# FeedbackLoop.net
KiCad netlist of a schematic drawn in Altium Designer
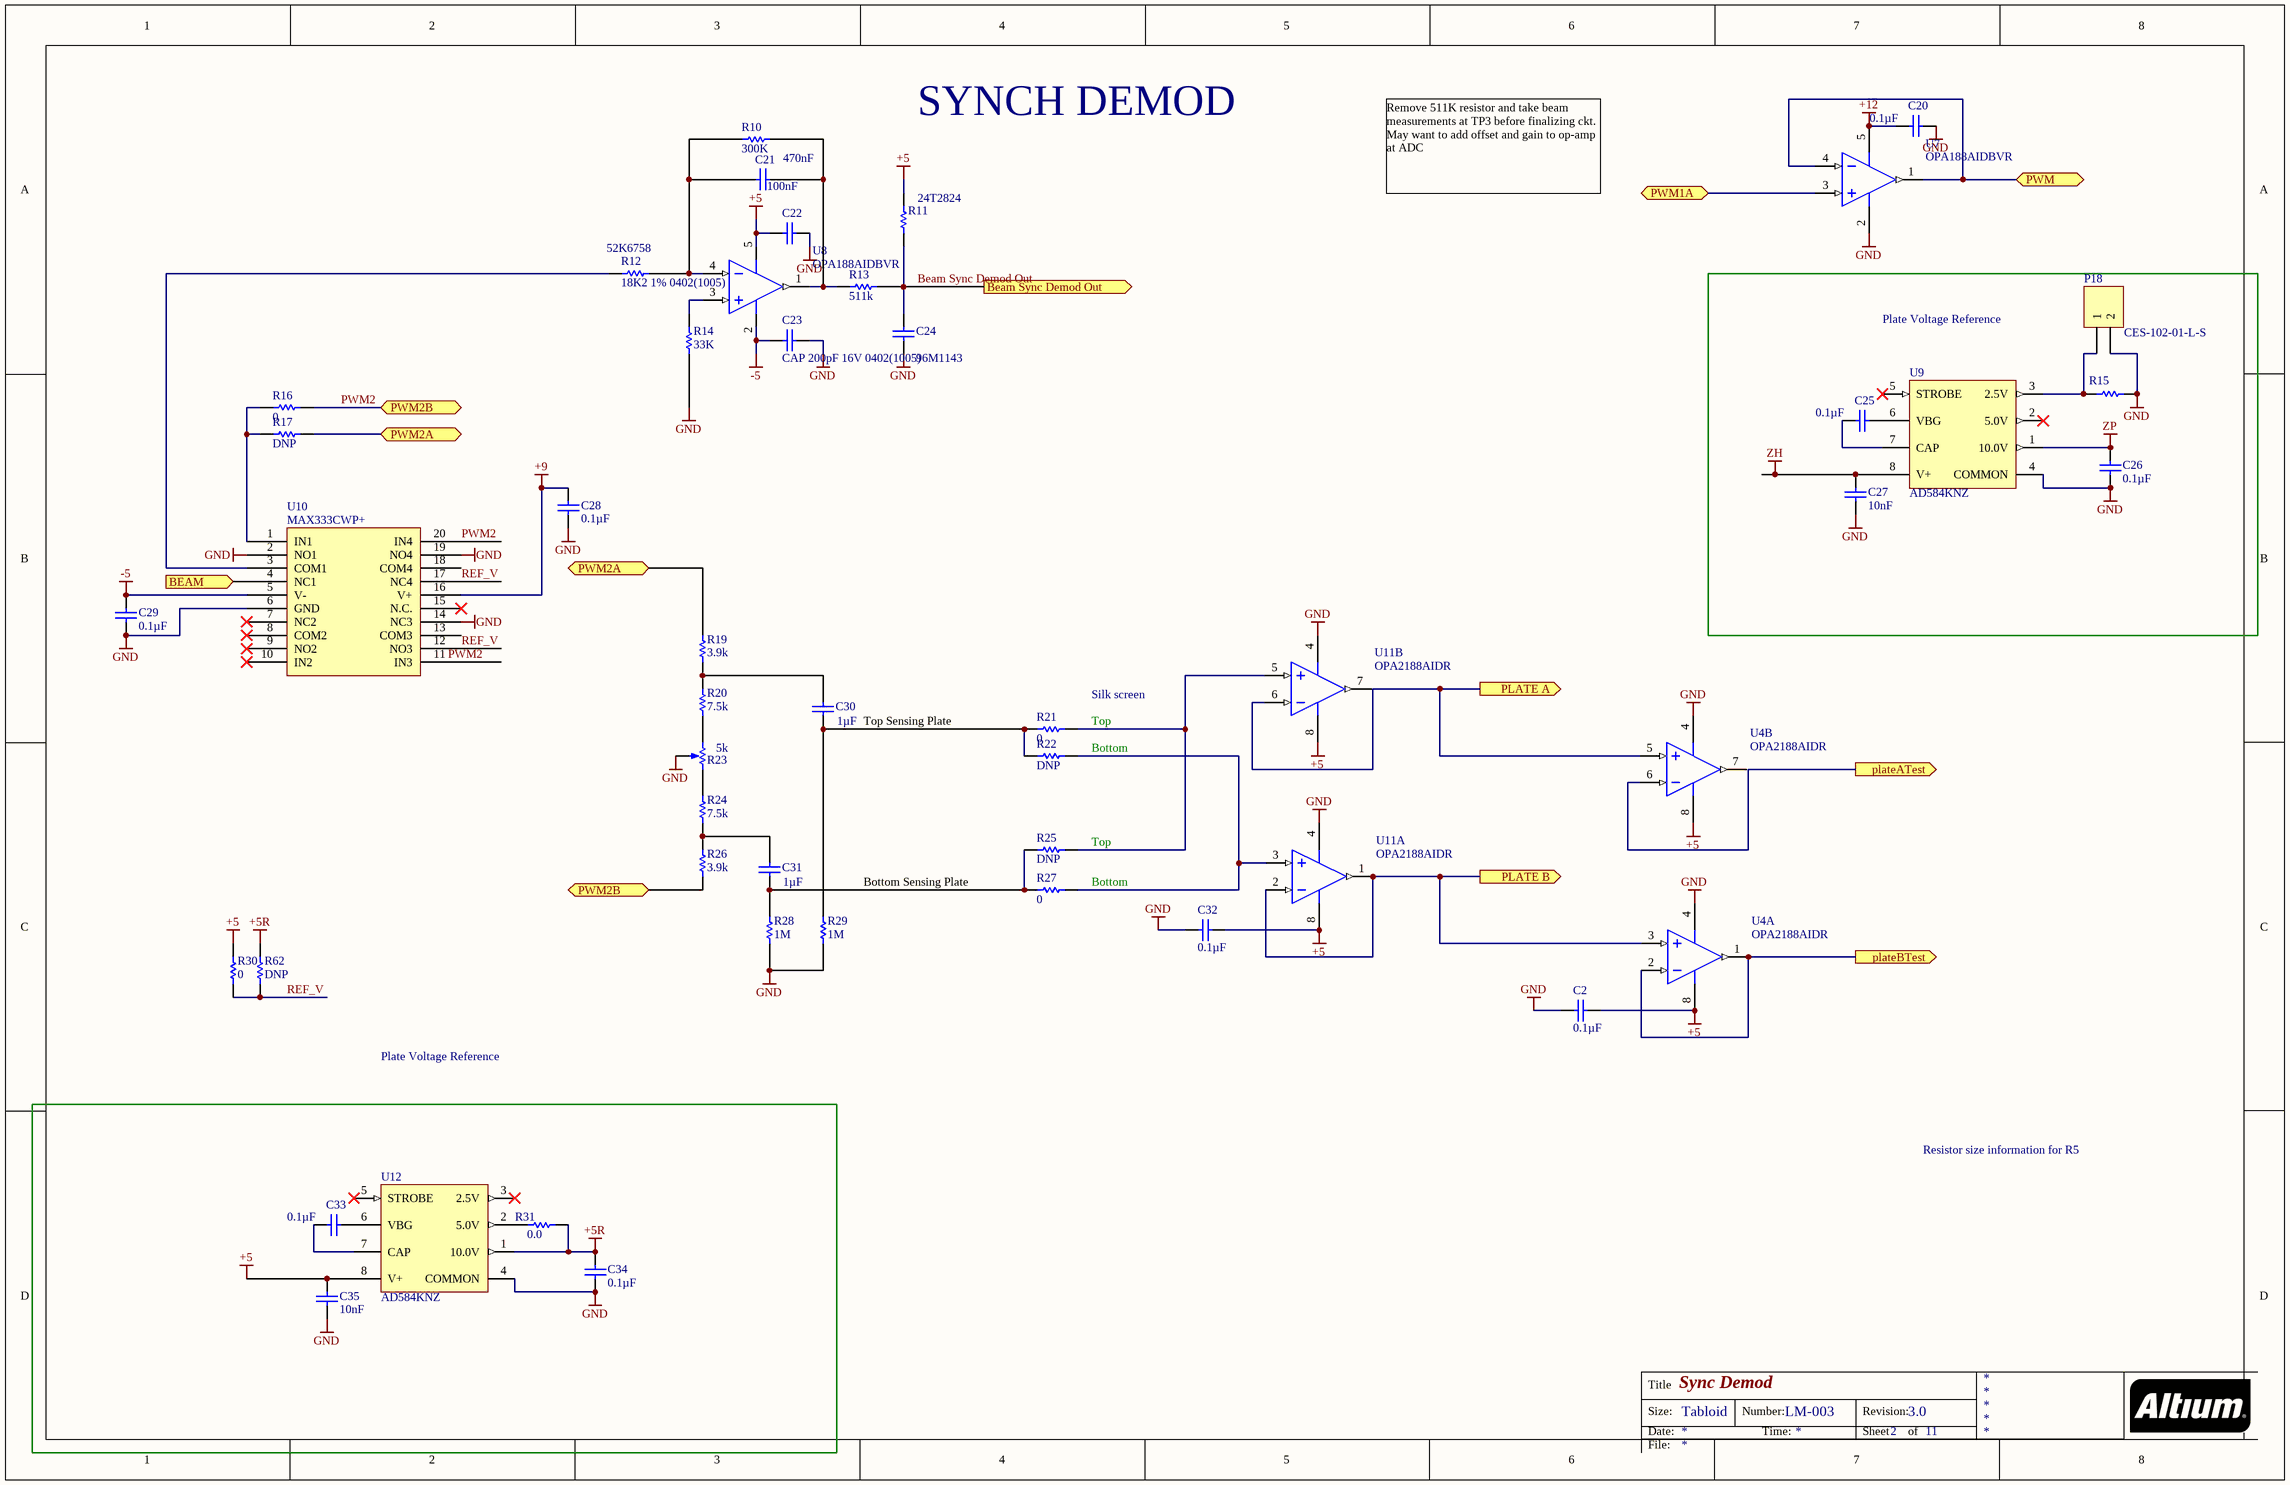
[diagram p0: FeedbackLoop.SchDoc]

(export (version "E")
  (design (tool "Eeschema 10.0.6"))
  (components
    (comp (ref "C2")
      (value "CAP CER 0.1UF 25V X7R 0805")
      (footprint "CAPC0805(2012)155_L")
      (fields
        (field (name "MANUFACTURER") "Murata Electronics North America")
        (field (name "MANUFACTURER PART NUMBER") "GRM21BR71E104KA01L")
        (field (name "CAPACITANCE") "0.1µF")
        (field (name "TOLERANCE") "±10%")
      )
      (libsource (lib "Altium Content Vault") (part "CMP-1036-04882-1"))
    )
    (comp (ref "C20")
      (value "CAP 100nF 25V 0805(2012)")
      (footprint "CAPC0805(2012)100_N")
      (description "CAP 100nF 25V -20% to +80% 0805 (2012 Metric) Thickness 1mm SMD")
      (fields
        (field (name "MANUFACTURER") "Murata Electronics North America")
        (field (name "MANUFACTURER PART NUMBER") "GRM21BR71E104KA01L")
        (field (name "CAPACITANCE") "0.1µF")
      )
      (libsource (lib "Altium Content Vault") (part "CMP-1036-04416-1"))
    )
    (comp (ref "C21")
      (value "~")
      (footprint "CAPC0402(1005)60_L")
      (fields
        (field (name "MANUFACTURER") "TDK")
        (field (name "MANUFACTURER PART NUMBER") "C1005X5R1E474M050BB")
        (field (name "TOLERANCE") "20%")
        (field (name "CAPACITANCE") "470nF")
      )
      (libsource (lib "Altium Content Vault") (part "CMP-1034-01343-1"))
    )
    (comp (ref "C22")
      (value "~")
      (footprint "CAPC0402(1005)60_L")
      (fields
        (field (name "MANUFACTURER") "Kemet")
        (field (name "MANUFACTURER PART NUMBER") "C0402C104K4RACAUTO")
        (field (name "CAPACITANCE") "100nF")
        (field (name "TOLERANCE") "10%")
      )
      (libsource (lib "Altium Content Vault") (part "CMP-1034-01343-1"))
    )
    (comp (ref "C23")
      (value "CAP 200pF 16V 0402(1005)")
      (footprint "CAPC0402(1005)60_L")
      (description "CAP 200pF 16V ±2% 0402 (1005 Metric) Thickness 0.6mm SMD")
      (fields (field (name "TOLERANCE") "Â±2%") (field (name "MANUFACTURER") "Kemet"))
      (libsource (lib "Altium Content Vault") (part "CMP-1034-01343-1"))
    )
    (comp (ref "C24")
      (value "~")
      (footprint "CAPC0402(1005)60_L")
      (fields
        (field (name "SUPPLIER PART NUMBER 1") "96M1143")
        (field (name "MANUFACTURER") "AVX")
        (field (name "MANUFACTURER PART NUMBER") "04025A220JAT2A")
      )
      (libsource (lib "Altium Content Vault") (part "CMP-1034-01343-1"))
    )
    (comp (ref "C25")
      (value "CAP 100nF 25V 0805(2012)")
      (footprint "CAPC0805(2012)100_N")
      (description "CAP 100nF 25V -20% to +80% 0805 (2012 Metric) Thickness 1mm SMD")
      (fields
        (field (name "MANUFACTURER") "Murata Electronics North America")
        (field (name "MANUFACTURER PART NUMBER") "GRM21BR71E104KA01L")
        (field (name "CAPACITANCE") "0.1µF")
      )
      (libsource (lib "Altium Content Vault") (part "CMP-1036-04416-1"))
    )
    (comp (ref "C26")
      (value "CAP CER 0.1UF 25V X7R 0805")
      (footprint "CAPC0805(2012)145_N")
      (fields
        (field (name "MANUFACTURER") "Murata Electronics North America")
        (field (name "MANUFACTURER PART NUMBER") "GRM21BR71E104KA01L")
        (field (name "CAPACITANCE") "0.1µF")
        (field (name "TOLERANCE") "±10%")
      )
      (libsource (lib "Altium Content Vault") (part "CMP-1036-04795-1"))
    )
    (comp (ref "C27")
      (value "Multilayer Ceramic Capacitors MLCC - SMD/SMT 0.01uF 50volts 10% X7R")
      (footprint "CAPC0805(2012)145_N")
      (fields
        (field (name "MANUFACTURER") "Kemet")
        (field (name "MANUFACTURER PART NUMBER") "C0805C103K5RACAUTO")
        (field (name "CAPACITANCE") "10nF")
        (field (name "TOLERANCE") "10%")
      )
      (libsource (lib "Altium Content Vault") (part "CMP-1036-04795-1"))
    )
    (comp (ref "C28")
      (value "CAP CER 0.1UF 25V X7R 0805")
      (footprint "CAPC0805(2012)145_N")
      (fields
        (field (name "MANUFACTURER") "Murata Electronics North America")
        (field (name "MANUFACTURER PART NUMBER") "GRM21BR71E104KA01L")
        (field (name "CAPACITANCE") "0.1µF")
        (field (name "TOLERANCE") "±10%")
      )
      (libsource (lib "Altium Content Vault") (part "CMP-1036-04795-1"))
    )
    (comp (ref "C29")
      (value "CAP CER 0.1UF 25V X7R 0805")
      (footprint "CAPC0805(2012)145_N")
      (fields
        (field (name "MANUFACTURER") "Murata Electronics North America")
        (field (name "MANUFACTURER PART NUMBER") "GRM21BR71E104KA01L")
        (field (name "CAPACITANCE") "0.1µF")
        (field (name "TOLERANCE") "±10%")
      )
      (libsource (lib "Altium Content Vault") (part "CMP-1036-04795-1"))
    )
    (comp (ref "C30")
      (value "CAP CER 1UF 25V X7R 0805")
      (footprint "CAPC0805(2012)155_L")
      (fields
        (field (name "MANUFACTURER") "Murata Electronics North America")
        (field (name "MANUFACTURER PART NUMBER") "GRM21BR71E105KA99L")
        (field (name "CAPACITANCE") "1µF")
        (field (name "TOLERANCE") "±10%")
      )
      (libsource (lib "Altium Content Vault") (part "CMP-1036-04882-1"))
    )
    (comp (ref "C31")
      (value "CAP CER 1UF 25V X7R 0805")
      (footprint "CAPC0805(2012)155_L")
      (fields
        (field (name "MANUFACTURER") "Murata Electronics North America")
        (field (name "MANUFACTURER PART NUMBER") "GRM21BR71E105KA99L")
        (field (name "CAPACITANCE") "1µF")
        (field (name "TOLERANCE") "±10%")
      )
      (libsource (lib "Altium Content Vault") (part "CMP-1036-04882-1"))
    )
    (comp (ref "C32")
      (value "CAP CER 0.1UF 25V X7R 0805")
      (footprint "CAPC0805(2012)155_L")
      (fields
        (field (name "MANUFACTURER") "Murata Electronics North America")
        (field (name "MANUFACTURER PART NUMBER") "GRM21BR71E104KA01L")
        (field (name "CAPACITANCE") "0.1µF")
        (field (name "TOLERANCE") "±10%")
      )
      (libsource (lib "Altium Content Vault") (part "CMP-1036-04882-1"))
    )
    (comp (ref "C33")
      (value "CAP 100nF 25V 0805(2012)")
      (footprint "CAPC0805(2012)100_N")
      (description "CAP 100nF 25V -20% to +80% 0805 (2012 Metric) Thickness 1mm SMD")
      (fields
        (field (name "MANUFACTURER") "Murata Electronics North America")
        (field (name "MANUFACTURER PART NUMBER") "GRM21BR71E104KA01L")
        (field (name "CAPACITANCE") "0.1µF")
      )
      (libsource (lib "Altium Content Vault") (part "CMP-1036-04416-1"))
    )
    (comp (ref "C34")
      (value "CAP CER 0.1UF 25V X7R 0805")
      (footprint "CAPC0805(2012)145_N")
      (fields
        (field (name "MANUFACTURER") "Murata Electronics North America")
        (field (name "MANUFACTURER PART NUMBER") "GRM21BR71E104KA01L")
        (field (name "CAPACITANCE") "0.1µF")
        (field (name "TOLERANCE") "±10%")
      )
      (libsource (lib "Altium Content Vault") (part "CMP-1036-04795-1"))
    )
    (comp (ref "C35")
      (value "Multilayer Ceramic Capacitors MLCC - SMD/SMT 0.01uF 50volts 10% X7R")
      (footprint "CAPC0805(2012)145_N")
      (fields
        (field (name "MANUFACTURER") "Kemet")
        (field (name "MANUFACTURER PART NUMBER") "C0805C103K5RACAUTO")
        (field (name "CAPACITANCE") "10nF")
        (field (name "TOLERANCE") "10%")
      )
      (libsource (lib "Altium Content Vault") (part "CMP-1036-04795-1"))
    )
    (comp (ref "P18")
      (value "LOW PROFILE .025\" SQUARE STRIPS")
      (footprint "CES-102-01-L-S")
      (fields
        (field (name "MANUFACTURER") "Samtec Inc.")
        (field (name "MANUFACTURER PART NUMBER") "CES-102-01-L-S")
      )
      (libsource (lib "Miscellaneous Connectors") (part "Header 2"))
    )
    (comp (ref "R10")
      (value "300K")
      (footprint "RESC0402(1005)_M")
      (libsource (lib "Altium Content Vault") (part "CMP-1011-00651-1"))
    )
    (comp (ref "R11")
      (value "~")
      (footprint "RESC0402(1005)_M")
      (fields
        (field (name "SUPPLIER PART NUMBER 1") "24T2824")
        (field (name "MANUFACTURER") "VISHAY")
        (field (name "MANUFACTURER PART NUMBER") "CRCW0402100KFKEDHP")
      )
      (libsource (lib "Altium Content Vault") (part "CMP-1011-00651-1"))
    )
    (comp (ref "R12")
      (value "18K2 1% 0402(1005)")
      (footprint "RESC0402(1005)_M")
      (description "18K2 0.063W 1% 0402 (1005 Metric)  SMD")
      (fields
        (field (name "SUPPLIER PART NUMBER 1") "52K6758")
        (field (name "MANUFACTURER") "VISHAY")
        (field (name "MANUFACTURER PART NUMBER") "CRCW040218K2FKED")
      )
      (libsource (lib "Altium Content Vault") (part "CMP-1011-00651-1"))
    )
    (comp (ref "R13")
      (value "511k")
      (footprint "RESC0402(1005)_M")
      (libsource (lib "Altium Content Vault") (part "CMP-1011-00651-1"))
    )
    (comp (ref "R14")
      (value "33K")
      (footprint "RESC0402(1005)_M")
      (libsource (lib "Altium Content Vault") (part "CMP-1011-00651-1"))
    )
    (comp (ref "R15")
      (value "TBD")
      (footprint "VH102K")
      (libsource (lib "altium-import") (part "root_0_CMP-1013-00393-1_"))
    )
    (comp (ref "R16")
      (value "0")
      (footprint "RESC0402(1005)_M")
      (libsource (lib "Altium Content Vault") (part "CMP-1011-00651-1"))
    )
    (comp (ref "R17")
      (value "DNP")
      (footprint "RESC0402(1005)_M")
      (libsource (lib "Altium Content Vault") (part "CMP-1011-00651-1"))
    )
    (comp (ref "R19")
      (value "3.9k")
      (footprint "RESC0402(1005)_M")
      (libsource (lib "Altium Content Vault") (part "CMP-1011-00651-1"))
    )
    (comp (ref "R20")
      (value "7.5k")
      (footprint "RESC0402(1005)_M")
      (libsource (lib "Altium Content Vault") (part "CMP-1011-00651-1"))
    )
    (comp (ref "R21")
      (value "0")
      (footprint "RESC0402(1005)_M")
      (libsource (lib "Altium Content Vault") (part "CMP-1011-00651-1"))
    )
    (comp (ref "R22")
      (value "DNP")
      (footprint "RESC0402(1005)_M")
      (libsource (lib "Altium Content Vault") (part "CMP-1011-00651-1"))
    )
    (comp (ref "R23")
      (value "TRIMMER 5K OHM 0.25W PC PIN")
      (footprint "Trimmer 2.54")
      (fields
        (field (name "MANUFACTURER") "Vishay Foil Resistors (Division of Vishay Precision Group)")
        (field (name "MANUFACTURER PART NUMBER") "Y00535K00000J0L")
        (field (name "RESISTANCE (OHMS)") "5k")
        (field (name "TOLERANCE") "±5%")
      )
      (libsource (lib "ZLS_Schematic_lib") (part "Trimmer"))
    )
    (comp (ref "R24")
      (value "7.5k")
      (footprint "RESC0402(1005)_M")
      (libsource (lib "Altium Content Vault") (part "CMP-1011-00651-1"))
    )
    (comp (ref "R25")
      (value "DNP")
      (footprint "RESC0402(1005)_M")
      (libsource (lib "Altium Content Vault") (part "CMP-1011-00651-1"))
    )
    (comp (ref "R26")
      (value "3.9k")
      (footprint "RESC0402(1005)_M")
      (libsource (lib "Altium Content Vault") (part "CMP-1011-00651-1"))
    )
    (comp (ref "R27")
      (value "0")
      (footprint "RESC0402(1005)_M")
      (libsource (lib "Altium Content Vault") (part "CMP-1011-00651-1"))
    )
    (comp (ref "R28")
      (value "1M")
      (footprint "RESC0402(1005)_M")
      (libsource (lib "Altium Content Vault") (part "CMP-1011-00651-1"))
    )
    (comp (ref "R29")
      (value "1M")
      (footprint "RESC0402(1005)_M")
      (libsource (lib "Altium Content Vault") (part "CMP-1011-00651-1"))
    )
    (comp (ref "R30")
      (value "0")
      (footprint "RESC0402(1005)_M")
      (libsource (lib "Altium Content Vault") (part "CMP-1011-00651-1"))
    )
    (comp (ref "R31")
      (value "RES SMD 0.0 OHM JUMPER 1/8W 0805")
      (footprint "RESC0805(2012)_M")
      (fields
        (field (name "MANUFACTURER") "Vishay Dale")
        (field (name "MANUFACTURER PART NUMBER") "CRCW08050000Z0EA")
        (field (name "RESISTANCE (OHMS)") "0.0")
        (field (name "TOLERANCE") "Jumper")
      )
      (libsource (lib "Altium Content Vault") (part "CMP-1013-00017-1"))
    )
    (comp (ref "R62")
      (value "DNP")
      (footprint "RESC0402(1005)_M")
      (libsource (lib "Altium Content Vault") (part "CMP-1011-00651-1"))
    )
    (comp (ref "U4")
      (value "OPA2188AIDR")
      (footprint "D0008A_L")
      (fields (field (name "MANUFACTURER") "Texas Instruments"))
      (libsource (lib "Altium Content Vault") (part "CMP-0272-00241-3"))
    )
    (comp (ref "U7")
      (value "OPA188AIDBVR")
      (footprint "DBV0005A_M")
      (fields (field (name "MANUFACTURER") "Texas Instruments"))
      (libsource (lib "Altium Content Vault") (part "CMP-0809-00005-2"))
    )
    (comp (ref "U8")
      (value "OPA188AIDBVR")
      (footprint "DBV0005A_M")
      (fields (field (name "MANUFACTURER") "Texas Instruments"))
      (libsource (lib "Altium Content Vault") (part "CMP-0809-00005-2"))
    )
    (comp (ref "U9")
      (value "AD584KNZ")
      (footprint "ADI-N-8")
      (fields (field (name "MANUFACTURER") "Analog Devices"))
      (libsource (lib "Altium Content Vault") (part "ADI-AD584-N-8"))
    )
    (comp (ref "U10")
      (value "MAX333CWP+")
      (footprint "TSOP65P640X90-20N")
      (description "IC SWITCH QUAD SPDT 20TSSOP")
      (fields (field (name "MANUFACTURER") "Maxim") (field (name "MANUFACTURER PART NUMBER") "MAX333AEUP+"))
      (libsource (lib "ZLS_Schematic_lib") (part "MAX333CWP+"))
    )
    (comp (ref "U11")
      (value "OPA2188AIDR")
      (footprint "D0008A_L")
      (fields (field (name "MANUFACTURER") "Texas Instruments"))
      (libsource (lib "Altium Content Vault") (part "CMP-0272-00241-3"))
    )
    (comp (ref "U12")
      (value "AD584KNZ")
      (footprint "ADI-N-8")
      (fields (field (name "MANUFACTURER") "Analog Devices"))
      (libsource (lib "Altium Content Vault") (part "ADI-AD584-N-8"))
    )
  )
  (nets
    (net (code "1") (name "+5") (class "Default")
      (node (ref "C2") (pin "1") (pinfunction "1_1") (pintype "passive"))
      (node (ref "C22") (pin "1") (pinfunction "1_1") (pintype "passive"))
      (node (ref "C32") (pin "1") (pinfunction "1_1") (pintype "passive"))
      (node (ref "C35") (pin "1") (pinfunction "1_1") (pintype "passive"))
      (node (ref "R11") (pin "2") (pinfunction "2_2") (pintype "passive"))
      (node (ref "R30") (pin "2") (pinfunction "2_2") (pintype "passive"))
      (node (ref "U11") (pin "8") (pinfunction "V+_8") (pintype "power_in"))
      (node (ref "U12") (pin "8") (pinfunction "V+_8") (pintype "power_in"))
      (node (ref "U4") (pin "8") (pinfunction "V+_8") (pintype "power_in"))
      (node (ref "U8") (pin "5") (pinfunction "V+_5") (pintype "power_in"))
    )
    (net (code "2") (name "+5R") (class "Default")
      (node (ref "C34") (pin "1") (pinfunction "1_1") (pintype "passive"))
      (node (ref "R31") (pin "1") (pinfunction "1_1") (pintype "passive"))
      (node (ref "R62") (pin "2") (pinfunction "2_2") (pintype "passive"))
      (node (ref "U12") (pin "1") (pinfunction "10.0V_1") (pintype "output"))
    )
    (net (code "3") (name "+9") (class "Default")
      (node (ref "C28") (pin "2") (pinfunction "2_2") (pintype "passive"))
      (node (ref "U10") (pin "16") (pinfunction "V+_16") (pintype "power_in"))
    )
    (net (code "4") (name "+12") (class "Default")
      (node (ref "C20") (pin "1") (pinfunction "1_1") (pintype "passive"))
      (node (ref "U7") (pin "5") (pinfunction "V+_5") (pintype "power_in"))
    )
    (net (code "5") (name "-5") (class "Default")
      (node (ref "C23") (pin "1") (pinfunction "1_1") (pintype "passive"))
      (node (ref "C29") (pin "1") (pinfunction "1_1") (pintype "passive"))
      (node (ref "U10") (pin "5") (pinfunction "V-_5") (pintype "power_in"))
      (node (ref "U8") (pin "2") (pinfunction "V-_2") (pintype "power_in"))
    )
    (net (code "6") (name "/BEAM") (class "Default")
      (node (ref "U10") (pin "4") (pinfunction "NC1_4") (pintype "passive"))
    )
    (net (code "7") (name "/Beam Sync Demod Out") (class "Default")
      (node (ref "C24") (pin "2") (pinfunction "2_2") (pintype "passive"))
      (node (ref "R11") (pin "1") (pinfunction "1_1") (pintype "passive"))
      (node (ref "R13") (pin "2") (pinfunction "2_2") (pintype "passive"))
    )
    (net (code "8") (name "/PLATE A") (class "Default")
      (node (ref "U11") (pin "6") (pinfunction "IN_B-_6") (pintype "input"))
      (node (ref "U4") (pin "5") (pinfunction "IN_B+_5") (pintype "input"))
    )
    (net (code "9") (name "/PLATE B") (class "Default")
      (node (ref "U11") (pin "1") (pinfunction "OUT_A_1") (pintype "output"))
      (node (ref "U11") (pin "2") (pinfunction "IN_A-_2") (pintype "input"))
      (node (ref "U4") (pin "3") (pinfunction "IN_A+_3") (pintype "input"))
    )
    (net (code "10") (name "/PWM") (class "Default")
      (node (ref "U7") (pin "1") (pinfunction "OUT_1") (pintype "output"))
      (node (ref "U7") (pin "4") (pinfunction "IN-_4") (pintype "input"))
    )
    (net (code "11") (name "/PWM1A") (class "Default")
      (node (ref "U7") (pin "3") (pinfunction "IN+_3") (pintype "input"))
    )
    (net (code "12") (name "/PWM2") (class "Default")
      (node (ref "R16") (pin "1") (pinfunction "1_1") (pintype "passive"))
      (node (ref "R26") (pin "1") (pinfunction "1_1") (pintype "passive"))
      (node (ref "U10") (pin "20") (pinfunction "IN4_20") (pintype "passive"))
    )
    (net (code "13") (name "/PWM2A") (class "Default")
      (node (ref "R17") (pin "1") (pinfunction "1_1") (pintype "passive"))
      (node (ref "R19") (pin "2") (pinfunction "2_2") (pintype "passive"))
    )
    (net (code "14") (name "/REF_V") (class "Default")
      (node (ref "R30") (pin "1") (pinfunction "1_1") (pintype "passive"))
      (node (ref "R62") (pin "1") (pinfunction "1_1") (pintype "passive"))
      (node (ref "U10") (pin "12") (pinfunction "NO3_12") (pintype "passive"))
      (node (ref "U10") (pin "17") (pinfunction "NC4_17") (pintype "passive"))
    )
    (net (code "15") (name "/plateATest") (class "Default")
      (node (ref "U4") (pin "6") (pinfunction "IN_B-_6") (pintype "input"))
    )
    (net (code "16") (name "/plateBTest") (class "Default")
      (node (ref "U4") (pin "1") (pinfunction "OUT_A_1") (pintype "output"))
      (node (ref "U4") (pin "2") (pinfunction "IN_A-_2") (pintype "input"))
    )
    (net (code "17") (name "GND") (class "Default")
      (node (ref "C2") (pin "2") (pinfunction "2_2") (pintype "passive"))
      (node (ref "C20") (pin "2") (pinfunction "2_2") (pintype "passive"))
      (node (ref "C22") (pin "2") (pinfunction "2_2") (pintype "passive"))
      (node (ref "C23") (pin "2") (pinfunction "2_2") (pintype "passive"))
      (node (ref "C24") (pin "1") (pinfunction "1_1") (pintype "passive"))
      (node (ref "C26") (pin "2") (pinfunction "2_2") (pintype "passive"))
      (node (ref "C27") (pin "2") (pinfunction "2_2") (pintype "passive"))
      (node (ref "C28") (pin "1") (pinfunction "1_1") (pintype "passive"))
      (node (ref "C29") (pin "2") (pinfunction "2_2") (pintype "passive"))
      (node (ref "C32") (pin "2") (pinfunction "2_2") (pintype "passive"))
      (node (ref "C34") (pin "2") (pinfunction "2_2") (pintype "passive"))
      (node (ref "C35") (pin "2") (pinfunction "2_2") (pintype "passive"))
      (node (ref "P18") (pin "2") (pinfunction "2_2") (pintype "passive"))
      (node (ref "R14") (pin "1") (pinfunction "1_1") (pintype "passive"))
      (node (ref "R15") (pin "2") (pinfunction "2_2") (pintype "passive"))
      (node (ref "R23") (pin "2") (pinfunction "b_2") (pintype "passive"))
      (node (ref "R28") (pin "1") (pinfunction "1_1") (pintype "passive"))
      (node (ref "R29") (pin "1") (pinfunction "1_1") (pintype "passive"))
      (node (ref "U10") (pin "14") (pinfunction "NC3_14") (pintype "passive"))
      (node (ref "U10") (pin "19") (pinfunction "NO4_19") (pintype "passive"))
      (node (ref "U10") (pin "2") (pinfunction "NO1_2") (pintype "passive"))
      (node (ref "U10") (pin "6") (pinfunction "GND_6") (pintype "passive"))
      (node (ref "U11") (pin "4") (pinfunction "V-_4") (pintype "power_in"))
      (node (ref "U12") (pin "4") (pinfunction "COMMON_4") (pintype "passive"))
      (node (ref "U4") (pin "4") (pinfunction "V-_4") (pintype "power_in"))
      (node (ref "U7") (pin "2") (pinfunction "V-_2") (pintype "power_in"))
      (node (ref "U9") (pin "4") (pinfunction "COMMON_4") (pintype "passive"))
    )
    (net (code "18") (name "Net-(C30-Pad1)") (class "Default")
      (node (ref "C30") (pin "1") (pinfunction "1_1") (pintype "passive"))
      (node (ref "R21") (pin "2") (pinfunction "2_2") (pintype "passive"))
      (node (ref "R22") (pin "2") (pinfunction "2_2") (pintype "passive"))
      (node (ref "R29") (pin "2") (pinfunction "2_2") (pintype "passive"))
    )
    (net (code "19") (name "Net-(C30-Pad2)") (class "Default")
      (node (ref "C30") (pin "2") (pinfunction "2_2") (pintype "passive"))
      (node (ref "R19") (pin "1") (pinfunction "1_1") (pintype "passive"))
      (node (ref "R20") (pin "2") (pinfunction "2_2") (pintype "passive"))
    )
    (net (code "20") (name "Net-(C31-Pad1)") (class "Default")
      (node (ref "C31") (pin "1") (pinfunction "1_1") (pintype "passive"))
      (node (ref "R25") (pin "2") (pinfunction "2_2") (pintype "passive"))
      (node (ref "R27") (pin "2") (pinfunction "2_2") (pintype "passive"))
      (node (ref "R28") (pin "2") (pinfunction "2_2") (pintype "passive"))
    )
    (net (code "21") (name "Net-(C31-Pad2)") (class "Default")
      (node (ref "C31") (pin "2") (pinfunction "2_2") (pintype "passive"))
      (node (ref "R24") (pin "1") (pinfunction "1_1") (pintype "passive"))
      (node (ref "R26") (pin "2") (pinfunction "2_2") (pintype "passive"))
    )
    (net (code "22") (name "Net-(R23-a)") (class "Default")
      (node (ref "R23") (pin "1") (pinfunction "a_1") (pintype "passive"))
      (node (ref "R24") (pin "2") (pinfunction "2_2") (pintype "passive"))
    )
    (net (code "23") (name "Net-(R23-c)") (class "Default")
      (node (ref "R20") (pin "1") (pinfunction "1_1") (pintype "passive"))
      (node (ref "R23") (pin "3") (pinfunction "c_3") (pintype "passive"))
    )
    (net (code "24") (name "Net-(U8-IN+)") (class "Default")
      (node (ref "R14") (pin "2") (pinfunction "2_2") (pintype "passive"))
      (node (ref "U8") (pin "3") (pinfunction "IN+_3") (pintype "input"))
    )
    (net (code "25") (name "Net-(U8-IN-)") (class "Default")
      (node (ref "C21") (pin "1") (pinfunction "1_1") (pintype "passive"))
      (node (ref "R10") (pin "1") (pinfunction "1_1") (pintype "passive"))
      (node (ref "R12") (pin "2") (pinfunction "2_2") (pintype "passive"))
      (node (ref "U8") (pin "4") (pinfunction "IN-_4") (pintype "input"))
    )
    (net (code "26") (name "Net-(U8-OUT)") (class "Default")
      (node (ref "C21") (pin "2") (pinfunction "2_2") (pintype "passive"))
      (node (ref "R10") (pin "2") (pinfunction "2_2") (pintype "passive"))
      (node (ref "R13") (pin "1") (pinfunction "1_1") (pintype "passive"))
      (node (ref "U8") (pin "1") (pinfunction "OUT_1") (pintype "output"))
    )
    (net (code "27") (name "Net-(U9-2.5V)") (class "Default")
      (node (ref "P18") (pin "1") (pinfunction "1_1") (pintype "passive"))
      (node (ref "R15") (pin "1") (pinfunction "1_1") (pintype "passive"))
      (node (ref "U9") (pin "3") (pinfunction "2.5V_3") (pintype "output"))
    )
    (net (code "28") (name "Net-(U9-CAP)") (class "Default")
      (node (ref "C25") (pin "1") (pinfunction "1_1") (pintype "passive"))
      (node (ref "U9") (pin "7") (pinfunction "CAP_7") (pintype "passive"))
    )
    (net (code "29") (name "Net-(U9-VBG)") (class "Default")
      (node (ref "C25") (pin "2") (pinfunction "2_2") (pintype "passive"))
      (node (ref "U9") (pin "6") (pinfunction "VBG_6") (pintype "passive"))
    )
    (net (code "30") (name "Net-(U10-COM1)") (class "Default")
      (node (ref "R12") (pin "1") (pinfunction "1_1") (pintype "passive"))
      (node (ref "U10") (pin "3") (pinfunction "COM1_3") (pintype "passive"))
    )
    (net (code "31") (name "Net-(U10-IN1)") (class "Default")
      (node (ref "R16") (pin "2") (pinfunction "2_2") (pintype "passive"))
      (node (ref "R17") (pin "2") (pinfunction "2_2") (pintype "passive"))
      (node (ref "U10") (pin "1") (pinfunction "IN1_1") (pintype "passive"))
    )
    (net (code "32") (name "Net-(U11A-IN_A+)") (class "Default")
      (node (ref "R22") (pin "1") (pinfunction "1_1") (pintype "passive"))
      (node (ref "R27") (pin "1") (pinfunction "1_1") (pintype "passive"))
      (node (ref "U11") (pin "3") (pinfunction "IN_A+_3") (pintype "input"))
    )
    (net (code "33") (name "Net-(U11B-IN_B+)") (class "Default")
      (node (ref "R21") (pin "1") (pinfunction "1_1") (pintype "passive"))
      (node (ref "R25") (pin "1") (pinfunction "1_1") (pintype "passive"))
      (node (ref "U11") (pin "5") (pinfunction "IN_B+_5") (pintype "input"))
    )
    (net (code "34") (name "Net-(U12-5.0V)") (class "Default")
      (node (ref "R31") (pin "2") (pinfunction "2_2") (pintype "passive"))
      (node (ref "U12") (pin "2") (pinfunction "5.0V_2") (pintype "output"))
    )
    (net (code "35") (name "Net-(U12-CAP)") (class "Default")
      (node (ref "C33") (pin "1") (pinfunction "1_1") (pintype "passive"))
      (node (ref "U12") (pin "7") (pinfunction "CAP_7") (pintype "passive"))
    )
    (net (code "36") (name "Net-(U12-VBG)") (class "Default")
      (node (ref "C33") (pin "2") (pinfunction "2_2") (pintype "passive"))
      (node (ref "U12") (pin "6") (pinfunction "VBG_6") (pintype "passive"))
    )
    (net (code "37") (name "ZH") (class "Default")
      (node (ref "C27") (pin "1") (pinfunction "1_1") (pintype "passive"))
      (node (ref "U9") (pin "8") (pinfunction "V+_8") (pintype "power_in"))
    )
    (net (code "38") (name "ZP") (class "Default")
      (node (ref "C26") (pin "1") (pinfunction "1_1") (pintype "passive"))
      (node (ref "U9") (pin "1") (pinfunction "10.0V_1") (pintype "output"))
    )
    (net (code "39") (name "unconnected-(U4B-OUT_B-Pad7)") (class "Default")
      (node (ref "U4") (pin "7") (pinfunction "OUT_B_7") (pintype "output"))
    )
    (net (code "40") (name "unconnected-(U9-5.0V-Pad2)") (class "Default")
      (node (ref "U9") (pin "2") (pinfunction "5.0V_2") (pintype "output+no_connect"))
    )
    (net (code "41") (name "unconnected-(U9-STROBE-Pad5)") (class "Default")
      (node (ref "U9") (pin "5") (pinfunction "STROBE_5") (pintype "input+no_connect"))
    )
    (net (code "42") (name "unconnected-(U10-COM2-Pad8)") (class "Default")
      (node (ref "U10") (pin "8") (pinfunction "COM2_8") (pintype "passive+no_connect"))
    )
    (net (code "43") (name "unconnected-(U10-COM3-Pad13)") (class "Default")
      (node (ref "U10") (pin "13") (pinfunction "COM3_13") (pintype "passive"))
    )
    (net (code "44") (name "unconnected-(U10-COM4-Pad18)") (class "Default")
      (node (ref "U10") (pin "18") (pinfunction "COM4_18") (pintype "passive"))
    )
    (net (code "45") (name "unconnected-(U10-IN2-Pad10)") (class "Default")
      (node (ref "U10") (pin "10") (pinfunction "IN2_10") (pintype "passive+no_connect"))
    )
    (net (code "46") (name "unconnected-(U10-IN3-Pad11)") (class "Default")
      (node (ref "U10") (pin "11") (pinfunction "IN3_11") (pintype "passive"))
    )
    (net (code "47") (name "unconnected-(U10-N.C.-Pad15)") (class "Default")
      (node (ref "U10") (pin "15") (pinfunction "N.C._15") (pintype "passive+no_connect"))
    )
    (net (code "48") (name "unconnected-(U10-NC2-Pad7)") (class "Default")
      (node (ref "U10") (pin "7") (pinfunction "NC2_7") (pintype "passive+no_connect"))
    )
    (net (code "49") (name "unconnected-(U10-NO2-Pad9)") (class "Default")
      (node (ref "U10") (pin "9") (pinfunction "NO2_9") (pintype "passive+no_connect"))
    )
    (net (code "50") (name "unconnected-(U11B-OUT_B-Pad7)") (class "Default")
      (node (ref "U11") (pin "7") (pinfunction "OUT_B_7") (pintype "output"))
    )
    (net (code "51") (name "unconnected-(U12-2.5V-Pad3)") (class "Default")
      (node (ref "U12") (pin "3") (pinfunction "2.5V_3") (pintype "output+no_connect"))
    )
    (net (code "52") (name "unconnected-(U12-STROBE-Pad5)") (class "Default")
      (node (ref "U12") (pin "5") (pinfunction "STROBE_5") (pintype "input+no_connect"))
    )
  )
)
